# Radar_Digital.net
KiCad netlist of a schematic drawn in Altium Designer
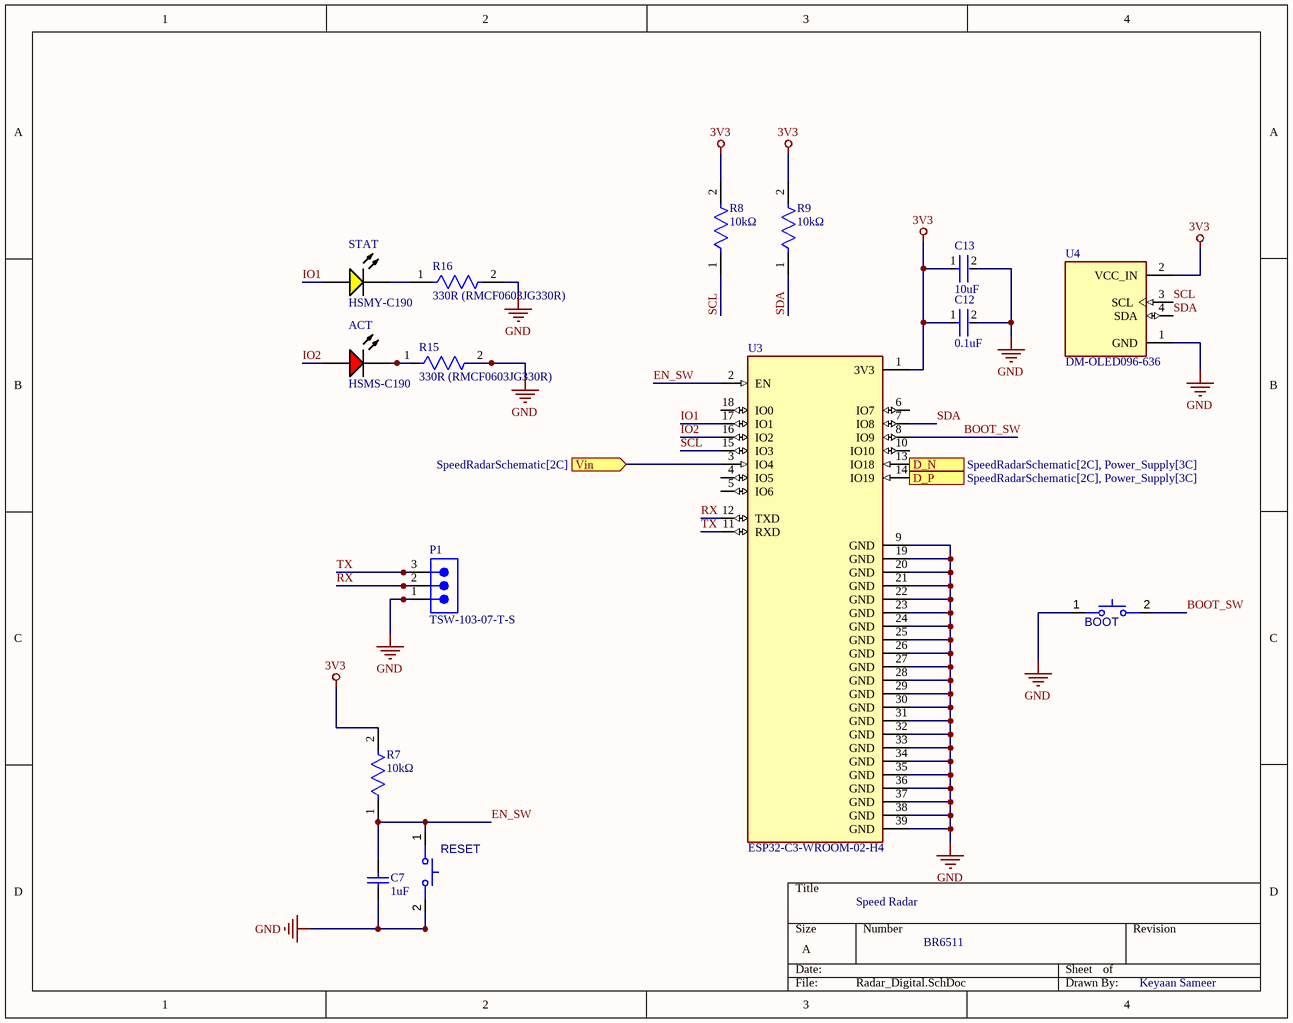
[diagram p0: Radar_Digital.SchDoc]

(export (version "E")
  (design (tool "Eeschema 10.0.6"))
  (components
    (comp (ref "ACT")
      (value "HSMS-C190")
      (footprint "AVAG-HSMX-C190_V")
      (description "LED Uni-Color Red, 52 mW, 20 mA, -40 to 85 degC, 2-Pin SMD, RoHS, Tape and Reel")
      (fields (field (name "MANUFACTURER") "Avago"))
      (libsource (lib "Altium Content Vault") (part "LED-RED-AK-2"))
    )
    (comp (ref "BOOT")
      (value "B3U-1000P-B")
      (footprint "OMRON-B3U-1000P-2-B_V")
      (libsource (lib "Dallas Formula Racing EV - University of Texas at Dallas") (part "CMP-00164-6"))
    )
    (comp (ref "C7")
      (value "1uF")
      (footprint "CAPC1608X90X35NL15T15")
      (fields
        (field (name "PART NUMBER") "0603YD105MAT2A")
        (field (name "MANUFACTURER") "AVX Interconnect / Elco")
      )
      (libsource (lib "Altium Content Vault") (part "CAP"))
    )
    (comp (ref "C12")
      (value "0.1uF")
      (footprint "FP-GCD21B-0_15-IPC_A")
      (fields (field (name "Comment") "GCD21BR71H104KA01L"))
      (libsource (lib "Dallas Formula Racing EV - University of Texas at Dallas") (part "b4654b650e69147ec39a6b967a45e02"))
    )
    (comp (ref "C13")
      (value "10uF")
      (footprint "FP-C0805C106K8RACAUTO-MFG")
      (description "CAP CER 10UF 10V X7R 0805")
      (fields (field (name "TOLERANCE") "10%"))
      (libsource (lib "Altium Content Vault") (part "b4654b650e69147ec39a6b967a45e02"))
    )
    (comp (ref "P1")
      (value "TSW-103-07-T-S")
      (footprint "SMTC-TSW-103-07-X-S")
      (description "0.025\" SQ Post Header, Through-hole, Vertical, -55 to 105 degC, 2.54 mm Pitch, 3-Pin, Male, RoHS")
      (fields (field (name "MANUFACTURER") "Samtec"))
      (libsource (lib "Altium Content Vault") (part "SMTC-TSW-103-X-X-S-X"))
    )
    (comp (ref "R7")
      (value "10kΩ")
      (footprint "FP-RQ732B-IPC_C")
      (description "RQ732B 1206 10KΩ 0.4W 10ppm/°C 0.1% 200V")
      (fields (field (name "MANUFACTURER") "TE") (field (name "MANUFACTURER PART NUMBER") "RQ73C2B10KBTD"))
      (libsource (lib "Altium Content Vault") (part "1029c3af85768c4190bb7ad29bc67b5"))
    )
    (comp (ref "R8")
      (value "10kΩ")
      (footprint "FP-RQ732B-IPC_C")
      (description "RQ732B 1206 10KΩ 0.4W 10ppm/°C 0.1% 200V")
      (fields (field (name "MANUFACTURER") "TE") (field (name "MANUFACTURER PART NUMBER") "RQ73C2B10KBTD"))
      (libsource (lib "Altium Content Vault") (part "1029c3af85768c4190bb7ad29bc67b5"))
    )
    (comp (ref "R9")
      (value "10kΩ")
      (footprint "FP-RQ732B-IPC_C")
      (description "RQ732B 1206 10KΩ 0.4W 10ppm/°C 0.1% 200V")
      (fields (field (name "MANUFACTURER") "TE") (field (name "MANUFACTURER PART NUMBER") "RQ73C2B10KBTD"))
      (libsource (lib "Altium Content Vault") (part "1029c3af85768c4190bb7ad29bc67b5"))
    )
    (comp (ref "R15")
      (value "330R (RMCF0603JG330R)")
      (footprint "FP-RMCF0603-IPC_B")
      (description "330Ω ±5% 0.1W 0603 Thick Film Chip Resistor AEC-Q200 compliant")
      (fields (field (name "TOLERANCE") "5%"))
      (libsource (lib "Altium Content Vault") (part "1029c3af85768c4190bb7ad29bc67b5"))
    )
    (comp (ref "R16")
      (value "330R (RMCF0603JG330R)")
      (footprint "FP-RMCF0603-IPC_B")
      (description "330Ω ±5% 0.1W 0603 Thick Film Chip Resistor AEC-Q200 compliant")
      (fields (field (name "TOLERANCE") "5%"))
      (libsource (lib "Altium Content Vault") (part "1029c3af85768c4190bb7ad29bc67b5"))
    )
    (comp (ref "RESET")
      (value "B3U-1000P-B")
      (footprint "OMRON-B3U-1000P-2-B_V")
      (libsource (lib "Dallas Formula Racing EV - University of Texas at Dallas") (part "CMP-00164-6"))
    )
    (comp (ref "STAT")
      (value "HSMY-C190")
      (footprint "AVAG-HSMX-C190_V")
      (description "LED Uni-Color Yellow, 65 mW, 20 mA, -40 to 85 degC, 2-Pin SMD, RoHS, Tape and Reel")
      (fields (field (name "TOLERANCE") "1%"))
      (libsource (lib "Altium Content Vault") (part "LED-YELLOW-AK-2"))
    )
    (comp (ref "U3")
      (value "ESP32-C3-WROOM-02-H4")
      (footprint "MODULE_ESP32-C3-WROOM-02-H4")
      (fields (field (name "MF") "Espressif Systems"))
      (libsource (lib "ESP32-C3-WROOM-02-H4") (part "ESP32-C3-WROOM-02-H4"))
    )
    (comp (ref "U4")
      (value "DM-OLED096-636")
      (footprint "MODULE_DM-OLED096-636")
      (description "0.96â€ 128 X 64 MONOCHROME GRAPHIC OLED DISPLAY MODULE - I2C")
      (fields (field (name "MF") "Display Module"))
      (libsource (lib "DM-OLED096-636") (part "DM-OLED096-636"))
    )
  )
  (nets
    (net (code "1") (name "/BOOT_SW") (class "Default")
      (node (ref "BOOT") (pin "2") (pinfunction "2_2") (pintype "passive"))
      (node (ref "U3") (pin "8") (pinfunction "IO9_8") (pintype "bidirectional"))
    )
    (net (code "2") (name "/D_N") (class "Default")
      (node (ref "U3") (pin "13") (pinfunction "IO18_13") (pintype "input"))
    )
    (net (code "3") (name "/D_P") (class "Default")
      (node (ref "U3") (pin "14") (pinfunction "IO19_14") (pintype "input"))
    )
    (net (code "4") (name "/EN_SW") (class "Default")
      (node (ref "C7") (pin "2") (pinfunction "2_2") (pintype "passive"))
      (node (ref "R7") (pin "1") (pinfunction "1_1") (pintype "passive"))
      (node (ref "RESET") (pin "1") (pinfunction "1_1") (pintype "passive"))
      (node (ref "U3") (pin "2") (pinfunction "EN_2") (pintype "input"))
    )
    (net (code "5") (name "/IO1") (class "Default")
      (node (ref "STAT") (pin "1") (pinfunction "A_1") (pintype "passive"))
      (node (ref "U3") (pin "17") (pinfunction "IO1_17") (pintype "bidirectional"))
    )
    (net (code "6") (name "/IO2") (class "Default")
      (node (ref "ACT") (pin "1") (pinfunction "A_1") (pintype "passive"))
      (node (ref "U3") (pin "16") (pinfunction "IO2_16") (pintype "bidirectional"))
    )
    (net (code "7") (name "/RX") (class "Default")
      (node (ref "P1") (pin "2") (pinfunction "2_2") (pintype "passive"))
      (node (ref "U3") (pin "12") (pinfunction "TXD_12") (pintype "bidirectional"))
    )
    (net (code "8") (name "/SCL") (class "Default")
      (node (ref "R8") (pin "1") (pinfunction "1_1") (pintype "passive"))
      (node (ref "U3") (pin "15") (pinfunction "IO3_15") (pintype "bidirectional"))
      (node (ref "U4") (pin "3") (pinfunction "SCL_3") (pintype "input"))
    )
    (net (code "9") (name "/SDA") (class "Default")
      (node (ref "R9") (pin "1") (pinfunction "1_1") (pintype "passive"))
      (node (ref "U3") (pin "7") (pinfunction "IO8_7") (pintype "bidirectional"))
      (node (ref "U4") (pin "4") (pinfunction "SDA_4") (pintype "bidirectional"))
    )
    (net (code "10") (name "/TX") (class "Default")
      (node (ref "P1") (pin "3") (pinfunction "3_3") (pintype "passive"))
      (node (ref "U3") (pin "11") (pinfunction "RXD_11") (pintype "bidirectional"))
    )
    (net (code "11") (name "/Vin") (class "Default")
      (node (ref "U3") (pin "3") (pinfunction "IO4_3") (pintype "input"))
    )
    (net (code "12") (name "3V3") (class "Default")
      (node (ref "C12") (pin "1") (pinfunction "1_1") (pintype "passive"))
      (node (ref "C13") (pin "1") (pinfunction "1_1") (pintype "passive"))
      (node (ref "R7") (pin "2") (pinfunction "2_2") (pintype "passive"))
      (node (ref "R8") (pin "2") (pinfunction "2_2") (pintype "passive"))
      (node (ref "R9") (pin "2") (pinfunction "2_2") (pintype "passive"))
      (node (ref "U3") (pin "1") (pinfunction "3V3_1") (pintype "power_in"))
      (node (ref "U4") (pin "2") (pinfunction "VCC_IN_2") (pintype "power_in"))
    )
    (net (code "13") (name "GND") (class "Default")
      (node (ref "BOOT") (pin "1") (pinfunction "1_1") (pintype "passive"))
      (node (ref "C12") (pin "2") (pinfunction "2_2") (pintype "passive"))
      (node (ref "C13") (pin "2") (pinfunction "2_2") (pintype "passive"))
      (node (ref "C7") (pin "1") (pinfunction "1_1") (pintype "passive"))
      (node (ref "P1") (pin "1") (pinfunction "1_1") (pintype "passive"))
      (node (ref "R15") (pin "2") (pinfunction "2_2") (pintype "passive"))
      (node (ref "R16") (pin "2") (pinfunction "2_2") (pintype "passive"))
      (node (ref "RESET") (pin "2") (pinfunction "2_2") (pintype "passive"))
      (node (ref "U3") (pin "19") (pinfunction "GND_19") (pintype "power_in"))
      (node (ref "U3") (pin "20") (pinfunction "GND_20") (pintype "power_in"))
      (node (ref "U3") (pin "21") (pinfunction "GND_21") (pintype "power_in"))
      (node (ref "U3") (pin "22") (pinfunction "GND_22") (pintype "power_in"))
      (node (ref "U3") (pin "23") (pinfunction "GND_23") (pintype "power_in"))
      (node (ref "U3") (pin "24") (pinfunction "GND_24") (pintype "power_in"))
      (node (ref "U3") (pin "25") (pinfunction "GND_25") (pintype "power_in"))
      (node (ref "U3") (pin "26") (pinfunction "GND_26") (pintype "power_in"))
      (node (ref "U3") (pin "27") (pinfunction "GND_27") (pintype "power_in"))
      (node (ref "U3") (pin "28") (pinfunction "GND_28") (pintype "power_in"))
      (node (ref "U3") (pin "29") (pinfunction "GND_29") (pintype "power_in"))
      (node (ref "U3") (pin "30") (pinfunction "GND_30") (pintype "power_in"))
      (node (ref "U3") (pin "31") (pinfunction "GND_31") (pintype "power_in"))
      (node (ref "U3") (pin "32") (pinfunction "GND_32") (pintype "power_in"))
      (node (ref "U3") (pin "33") (pinfunction "GND_33") (pintype "power_in"))
      (node (ref "U3") (pin "34") (pinfunction "GND_34") (pintype "power_in"))
      (node (ref "U3") (pin "35") (pinfunction "GND_35") (pintype "power_in"))
      (node (ref "U3") (pin "36") (pinfunction "GND_36") (pintype "power_in"))
      (node (ref "U3") (pin "37") (pinfunction "GND_37") (pintype "power_in"))
      (node (ref "U3") (pin "38") (pinfunction "GND_38") (pintype "power_in"))
      (node (ref "U3") (pin "39") (pinfunction "GND_39") (pintype "power_in"))
      (node (ref "U3") (pin "9") (pinfunction "GND_9") (pintype "power_in"))
      (node (ref "U4") (pin "1") (pinfunction "GND_1") (pintype "power_in"))
    )
    (net (code "14") (name "Net-(ACT-K)") (class "Default")
      (node (ref "ACT") (pin "2") (pinfunction "K_2") (pintype "passive"))
      (node (ref "R15") (pin "1") (pinfunction "1_1") (pintype "passive"))
    )
    (net (code "15") (name "Net-(STAT-K)") (class "Default")
      (node (ref "R16") (pin "1") (pinfunction "1_1") (pintype "passive"))
      (node (ref "STAT") (pin "2") (pinfunction "K_2") (pintype "passive"))
    )
    (net (code "16") (name "unconnected-(U3-IO0-Pad18)") (class "Default")
      (node (ref "U3") (pin "18") (pinfunction "IO0_18") (pintype "bidirectional"))
    )
    (net (code "17") (name "unconnected-(U3-IO5-Pad4)") (class "Default")
      (node (ref "U3") (pin "4") (pinfunction "IO5_4") (pintype "bidirectional"))
    )
    (net (code "18") (name "unconnected-(U3-IO6-Pad5)") (class "Default")
      (node (ref "U3") (pin "5") (pinfunction "IO6_5") (pintype "bidirectional"))
    )
    (net (code "19") (name "unconnected-(U3-IO7-Pad6)") (class "Default")
      (node (ref "U3") (pin "6") (pinfunction "IO7_6") (pintype "bidirectional"))
    )
    (net (code "20") (name "unconnected-(U3-IO10-Pad10)") (class "Default")
      (node (ref "U3") (pin "10") (pinfunction "IO10_10") (pintype "bidirectional"))
    )
  )
)
